# Student_Arm.net
KiCad netlist of a schematic drawn in Altium Designer
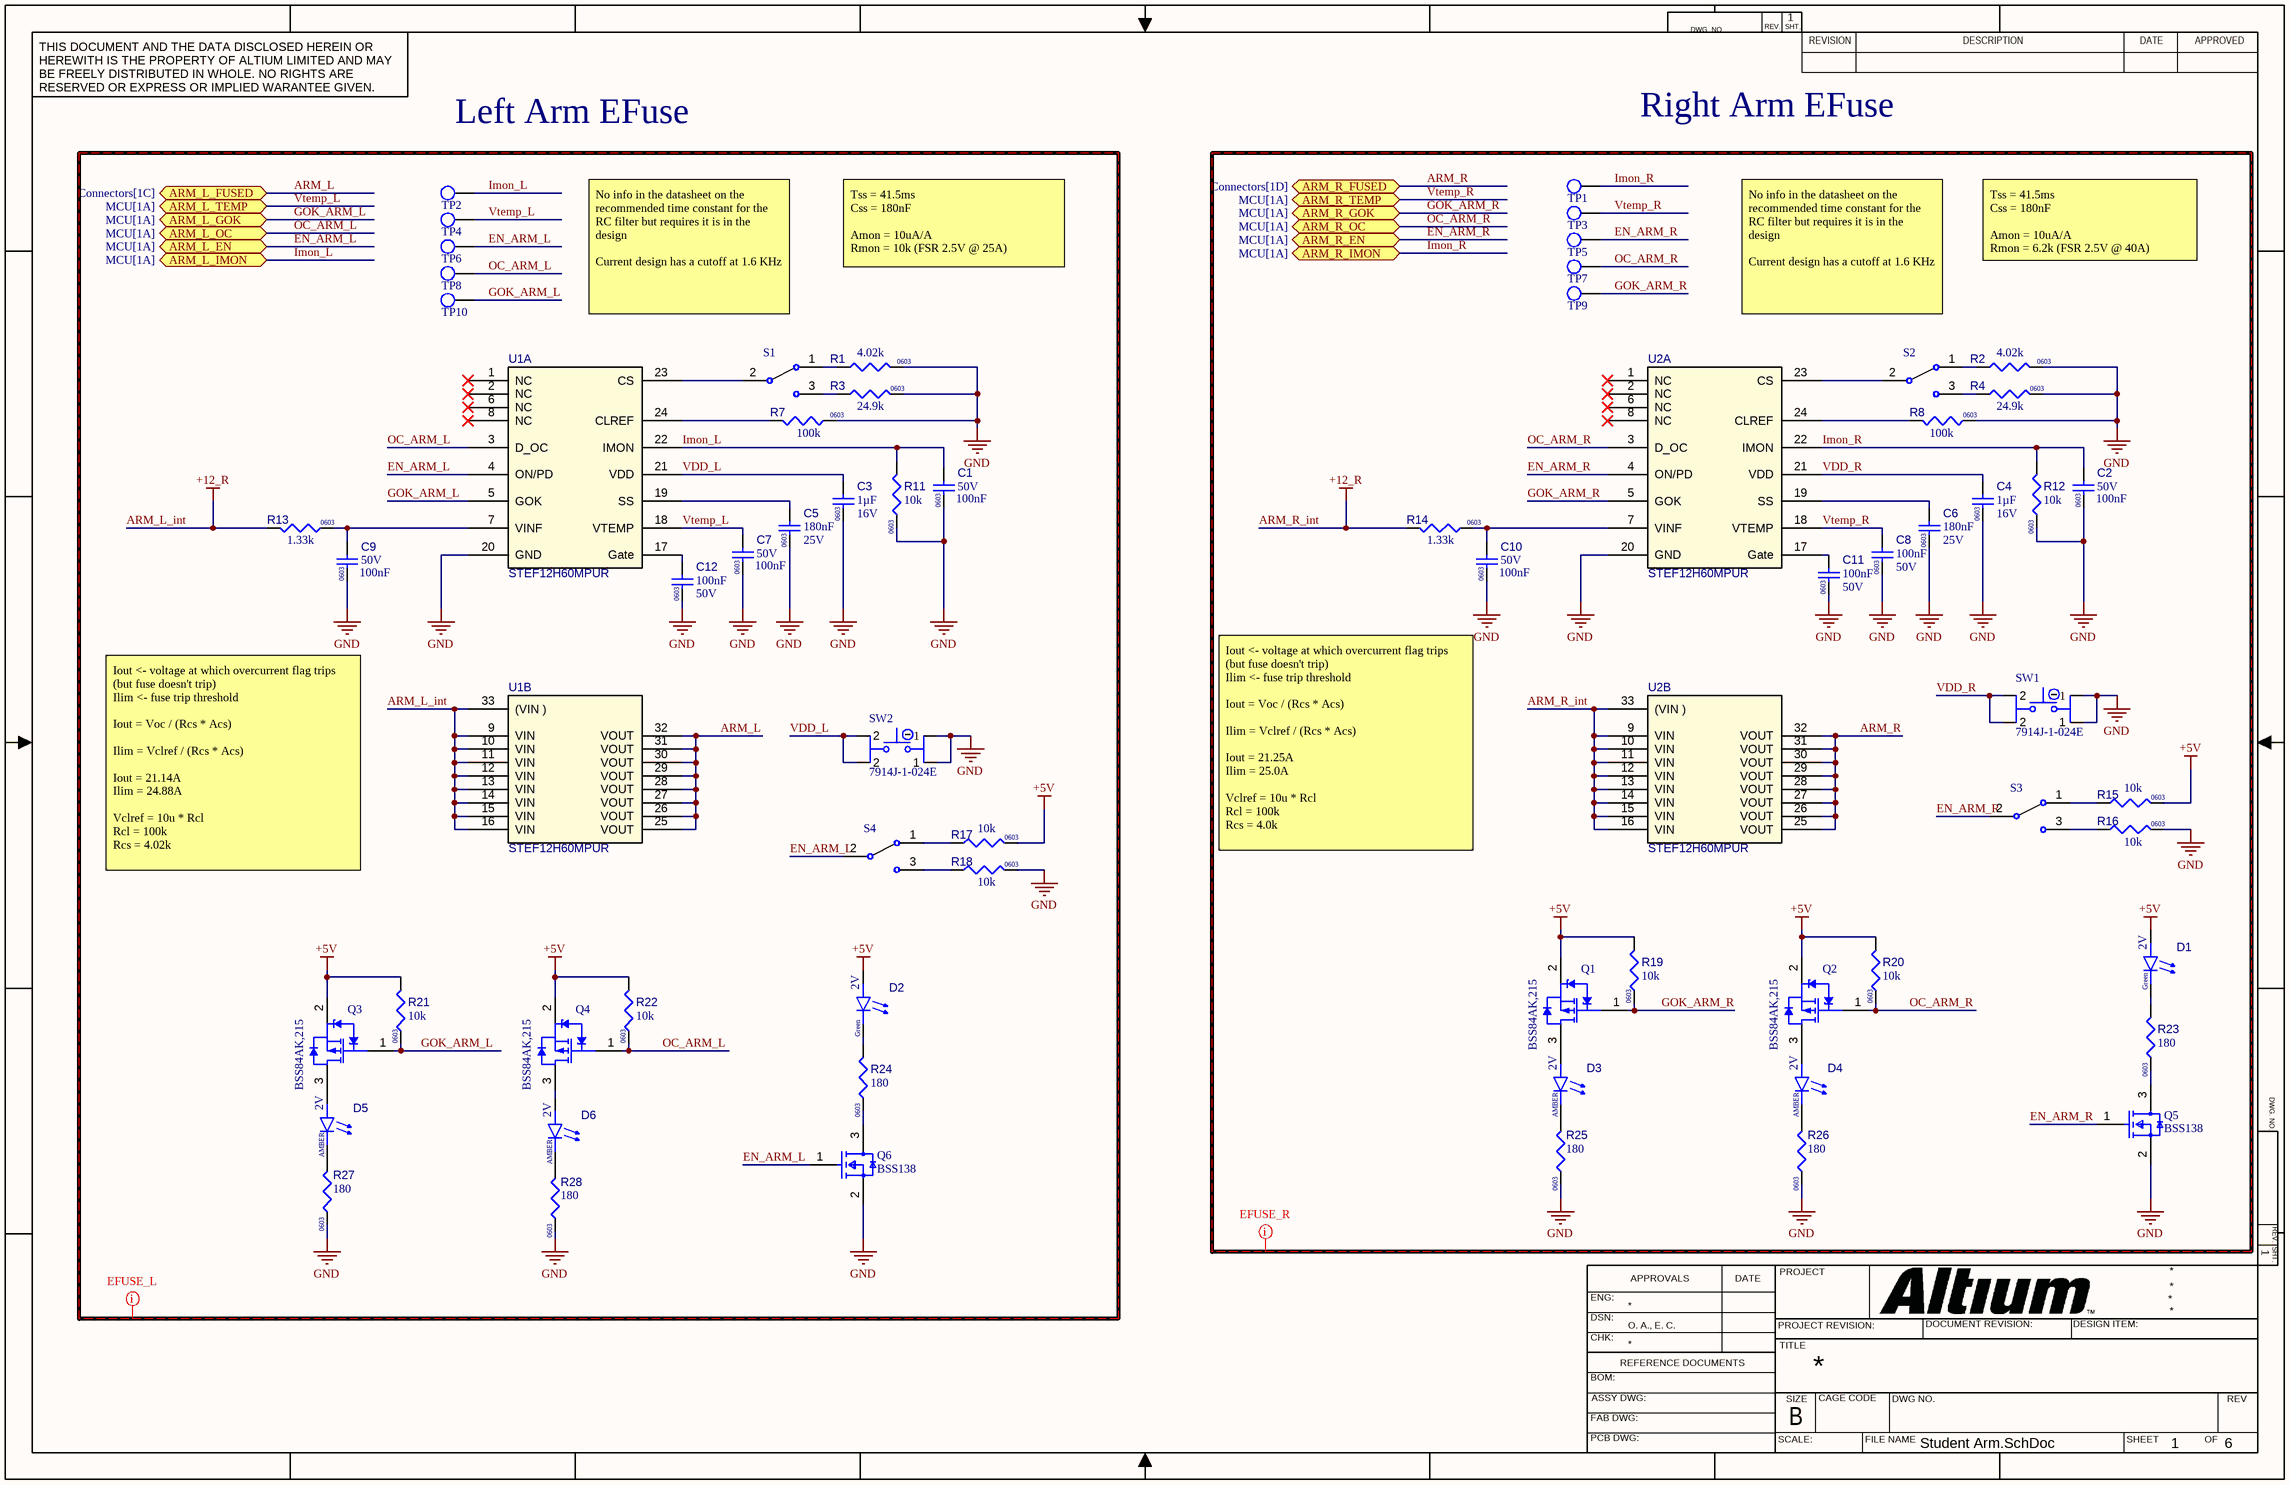
[diagram p0: Student Arm.SchDoc]

(export (version "E")
  (design (tool "Eeschema 10.0.6"))
  (components
    (comp (ref "C1")
      (value "100nF")
      (footprint "CAPC1608X90X40NL10T20")
      (description "Chip Capacitor, 100 nF, +/- 10%, 50 V, 0603 (1608 Metric)")
      (fields
        (field (name "TOLERANCE") "10%")
        (field (name "VOLTAGE RATING") "50V")
        (field (name "CASE/PACKAGE") "0603")
        (field (name "Comment") "Capacitor 100 nF +/-10% 50 V 0603")
      )
      (libsource (lib "hawaiirobotics") (part "CAP-NP-2"))
    )
    (comp (ref "C2")
      (value "100nF")
      (footprint "CAPC1608X90X40NL10T20")
      (description "Chip Capacitor, 100 nF, +/- 10%, 50 V, 0603 (1608 Metric)")
      (fields
        (field (name "TOLERANCE") "10%")
        (field (name "VOLTAGE RATING") "50V")
        (field (name "CASE/PACKAGE") "0603")
        (field (name "Comment") "Capacitor 100 nF +/-10% 50 V 0603")
      )
      (libsource (lib "hawaiirobotics") (part "CAP-NP-2"))
    )
    (comp (ref "C3")
      (value "1µF")
      (footprint "CAPC1608X90X35NL15T15")
      (description "Chip Capacitor, 1 uF, +/- 10%, 16 V, 0603 (1608 Metric)")
      (fields
        (field (name "CASE/PACKAGE") "0603")
        (field (name "TOLERANCE") "10%")
        (field (name "VOLTAGE RATING") "16V")
        (field (name "Comment") "Capacitor 1uF +/- 10% 16V 0603")
      )
      (libsource (lib "hawaiirobotics") (part "CAP-NP-2"))
    )
    (comp (ref "C4")
      (value "1µF")
      (footprint "CAPC1608X90X35NL15T15")
      (description "Chip Capacitor, 1 uF, +/- 10%, 16 V, 0603 (1608 Metric)")
      (fields
        (field (name "CASE/PACKAGE") "0603")
        (field (name "TOLERANCE") "10%")
        (field (name "VOLTAGE RATING") "16V")
        (field (name "Comment") "Capacitor 1uF +/- 10% 16V 0603")
      )
      (libsource (lib "hawaiirobotics") (part "CAP-NP-2"))
    )
    (comp (ref "C5")
      (value "180nF")
      (footprint "FP-GCM188-0_1-IPC_C")
      (fields
        (field (name "CASE/PACKAGE") "0603")
        (field (name "RATED DC VOLTAGE (URDC)") "25V")
        (field (name "Comment") "GCM188R71E184KA55D")
      )
      (libsource (lib "hawaiirobotics") (part "CAP-NP-2"))
    )
    (comp (ref "C6")
      (value "180nF")
      (footprint "FP-GCM188-0_1-IPC_C")
      (fields
        (field (name "CASE/PACKAGE") "0603")
        (field (name "RATED DC VOLTAGE (URDC)") "25V")
        (field (name "Comment") "GCM188R71E184KA55D")
      )
      (libsource (lib "hawaiirobotics") (part "CAP-NP-2"))
    )
    (comp (ref "C7")
      (value "100nF")
      (footprint "CAPC1608X90X40NL10T20")
      (description "Chip Capacitor, 100 nF, +/- 10%, 50 V, 0603 (1608 Metric)")
      (fields
        (field (name "TOLERANCE") "10%")
        (field (name "VOLTAGE RATING") "50V")
        (field (name "CASE/PACKAGE") "0603")
        (field (name "Comment") "Capacitor 100 nF +/-10% 50 V 0603")
      )
      (libsource (lib "hawaiirobotics") (part "CAP-NP-2"))
    )
    (comp (ref "C8")
      (value "100nF")
      (footprint "CAPC1608X90X40NL10T20")
      (description "Chip Capacitor, 100 nF, +/- 10%, 50 V, 0603 (1608 Metric)")
      (fields
        (field (name "TOLERANCE") "10%")
        (field (name "VOLTAGE RATING") "50V")
        (field (name "CASE/PACKAGE") "0603")
        (field (name "Comment") "Capacitor 100 nF +/-10% 50 V 0603")
      )
      (libsource (lib "hawaiirobotics") (part "CAP-NP-2"))
    )
    (comp (ref "C9")
      (value "100nF")
      (footprint "CAPC1608X90X40NL10T20")
      (description "Chip Capacitor, 100 nF, +/- 10%, 50 V, 0603 (1608 Metric)")
      (fields
        (field (name "TOLERANCE") "10%")
        (field (name "VOLTAGE RATING") "50V")
        (field (name "CASE/PACKAGE") "0603")
        (field (name "Comment") "Capacitor 100 nF +/-10% 50 V 0603")
      )
      (libsource (lib "hawaiirobotics") (part "CAP-NP-2"))
    )
    (comp (ref "C10")
      (value "100nF")
      (footprint "CAPC1608X90X40NL10T20")
      (description "Chip Capacitor, 100 nF, +/- 10%, 50 V, 0603 (1608 Metric)")
      (fields
        (field (name "TOLERANCE") "10%")
        (field (name "VOLTAGE RATING") "50V")
        (field (name "CASE/PACKAGE") "0603")
        (field (name "Comment") "Capacitor 100 nF +/-10% 50 V 0603")
      )
      (libsource (lib "hawaiirobotics") (part "CAP-NP-2"))
    )
    (comp (ref "C11")
      (value "100nF")
      (footprint "CAPC1608X90X40NL10T20")
      (description "Chip Capacitor, 100 nF, +/- 10%, 50 V, 0603 (1608 Metric)")
      (fields
        (field (name "TOLERANCE") "10%")
        (field (name "VOLTAGE RATING") "50V")
        (field (name "CASE/PACKAGE") "0603")
        (field (name "Comment") "Capacitor 100 nF +/-10% 50 V 0603")
      )
      (libsource (lib "hawaiirobotics") (part "CAP-NP-2"))
    )
    (comp (ref "C12")
      (value "100nF")
      (footprint "CAPC1608X90X40NL10T20")
      (description "Chip Capacitor, 100 nF, +/- 10%, 50 V, 0603 (1608 Metric)")
      (fields
        (field (name "TOLERANCE") "10%")
        (field (name "VOLTAGE RATING") "50V")
        (field (name "CASE/PACKAGE") "0603")
        (field (name "Comment") "Capacitor 100 nF +/-10% 50 V 0603")
      )
      (libsource (lib "hawaiirobotics") (part "CAP-NP-2"))
    )
    (comp (ref "D1")
      (value "150060VS75000")
      (footprint "WL-SMCW_0603_150060xx75000")
      (description "Single Color LED, Bright Green, Water Clear, 1.1mm")
      (fields (field (name "FORWARD VOLTAGE") "2V") (field (name "COLOR") "Green"))
      (libsource (lib "hawaiirobotics") (part "DIODE-LED-2"))
    )
    (comp (ref "D2")
      (value "150060VS75000")
      (footprint "WL-SMCW_0603_150060xx75000")
      (description "Single Color LED, Bright Green, Water Clear, 1.1mm")
      (fields (field (name "FORWARD VOLTAGE") "2V") (field (name "COLOR") "Green"))
      (libsource (lib "hawaiirobotics") (part "DIODE-LED-2"))
    )
    (comp (ref "D3")
      (value "150060AS75000")
      (footprint "WL-SMCW_0603_150060xx75000")
      (description "Single Color LED, Amber, Water Clear, 1.1mm")
      (fields (field (name "FORWARD VOLTAGE") "2V") (field (name "COLOUR") "AMBER"))
      (libsource (lib "hawaiirobotics") (part "DIODE-LED-2"))
    )
    (comp (ref "D4")
      (value "150060AS75000")
      (footprint "WL-SMCW_0603_150060xx75000")
      (description "Single Color LED, Amber, Water Clear, 1.1mm")
      (fields (field (name "FORWARD VOLTAGE") "2V") (field (name "COLOUR") "AMBER"))
      (libsource (lib "hawaiirobotics") (part "DIODE-LED-2"))
    )
    (comp (ref "D5")
      (value "150060AS75000")
      (footprint "WL-SMCW_0603_150060xx75000")
      (description "Single Color LED, Amber, Water Clear, 1.1mm")
      (fields (field (name "FORWARD VOLTAGE") "2V") (field (name "COLOUR") "AMBER"))
      (libsource (lib "hawaiirobotics") (part "DIODE-LED-2"))
    )
    (comp (ref "D6")
      (value "150060AS75000")
      (footprint "WL-SMCW_0603_150060xx75000")
      (description "Single Color LED, Amber, Water Clear, 1.1mm")
      (fields (field (name "FORWARD VOLTAGE") "2V") (field (name "COLOUR") "AMBER"))
      (libsource (lib "hawaiirobotics") (part "DIODE-LED-2"))
    )
    (comp (ref "Q1")
      (value "BSS84AK,215")
      (footprint "NXP-SOT23_N")
      (description "P-Channel Trench MOSFET, -50 V, -0.18 A, -55 to 150 degC, 3-Pin SOT23, Tape and Reel")
      (fields (field (name "MANUFACTURER") "NXP Semiconductors"))
      (libsource (lib "Altium Content Vault") (part "NXP-PMOS-GSD-3_B"))
    )
    (comp (ref "Q2")
      (value "BSS84AK,215")
      (footprint "NXP-SOT23_N")
      (description "P-Channel Trench MOSFET, -50 V, -0.18 A, -55 to 150 degC, 3-Pin SOT23, Tape and Reel")
      (fields (field (name "MANUFACTURER") "NXP Semiconductors"))
      (libsource (lib "Altium Content Vault") (part "NXP-PMOS-GSD-3_B"))
    )
    (comp (ref "Q3")
      (value "BSS84AK,215")
      (footprint "NXP-SOT23_N")
      (description "P-Channel Trench MOSFET, -50 V, -0.18 A, -55 to 150 degC, 3-Pin SOT23, Tape and Reel")
      (fields (field (name "MANUFACTURER") "NXP Semiconductors"))
      (libsource (lib "Altium Content Vault") (part "NXP-PMOS-GSD-3_B"))
    )
    (comp (ref "Q4")
      (value "BSS84AK,215")
      (footprint "NXP-SOT23_N")
      (description "P-Channel Trench MOSFET, -50 V, -0.18 A, -55 to 150 degC, 3-Pin SOT23, Tape and Reel")
      (fields (field (name "MANUFACTURER") "NXP Semiconductors"))
      (libsource (lib "Altium Content Vault") (part "NXP-PMOS-GSD-3_B"))
    )
    (comp (ref "Q5")
      (value "BSS138")
      (footprint "FP-318-08-IPC_B")
      (description "MOSFET N-CH 50V 220MA SOT-23")
      (libsource (lib "Altium Content Vault") (part "3b9c635fedb024a5347a57b145af9cc"))
    )
    (comp (ref "Q6")
      (value "BSS138")
      (footprint "FP-318-08-IPC_B")
      (description "MOSFET N-CH 50V 220MA SOT-23")
      (libsource (lib "Altium Content Vault") (part "3b9c635fedb024a5347a57b145af9cc"))
    )
    (comp (ref "R1")
      (value "4.02k")
      (footprint "RESC1608X55X25NL10T15")
      (fields
        (field (name "TOLERANCE") "1%")
        (field (name "POWER") "100mW")
        (field (name "CASE/PACKAGE") "0603")
        (field (name "Comment") "RC0603FR-074K02L")
      )
      (libsource (lib "hawaiirobotics") (part "RES-2"))
    )
    (comp (ref "R2")
      (value "4.02k")
      (footprint "RESC1608X55X25NL10T15")
      (fields
        (field (name "TOLERANCE") "1%")
        (field (name "POWER") "100mW")
        (field (name "CASE/PACKAGE") "0603")
        (field (name "Comment") "RC0603FR-074K02L")
      )
      (libsource (lib "hawaiirobotics") (part "RES-2"))
    )
    (comp (ref "R3")
      (value "24.9k")
      (footprint "RESC1608X55X25NL10T15")
      (fields
        (field (name "POWER") "100mW")
        (field (name "TOLERANCE") "1%")
        (field (name "CASE/PACKAGE") "0603")
        (field (name "Comment") "RC0603FR-1024K9L")
      )
      (libsource (lib "hawaiirobotics") (part "RES-2"))
    )
    (comp (ref "R4")
      (value "24.9k")
      (footprint "RESC1608X55X25NL10T15")
      (fields
        (field (name "POWER") "100mW")
        (field (name "TOLERANCE") "1%")
        (field (name "CASE/PACKAGE") "0603")
        (field (name "Comment") "RC0603FR-1024K9L")
      )
      (libsource (lib "hawaiirobotics") (part "RES-2"))
    )
    (comp (ref "R7")
      (value "100k")
      (footprint "RESC1608X55X25NL10T15")
      (fields
        (field (name "POWER") "100mW")
        (field (name "TOLERANCE") "1%")
        (field (name "CASE/PACKAGE") "0603")
        (field (name "Comment") "RC0603FR-07100KL")
      )
      (libsource (lib "hawaiirobotics") (part "RES-2"))
    )
    (comp (ref "R8")
      (value "100k")
      (footprint "RESC1608X55X25NL10T15")
      (fields
        (field (name "POWER") "100mW")
        (field (name "TOLERANCE") "1%")
        (field (name "CASE/PACKAGE") "0603")
        (field (name "Comment") "RC0603FR-07100KL")
      )
      (libsource (lib "hawaiirobotics") (part "RES-2"))
    )
    (comp (ref "R11")
      (value "10k")
      (footprint "RESC1608X55X25NL10T15")
      (description "Chip Resistor, 10 KOhm, +/- 1%, 01 W, -55 to 155 degC, 0603 (1608 Metric)")
      (fields
        (field (name "CASE/PACKAGE") "0603")
        (field (name "POWER") "100mW")
        (field (name "TOLERANCE") "1%")
      )
      (libsource (lib "hawaiirobotics") (part "RES-2"))
    )
    (comp (ref "R12")
      (value "10k")
      (footprint "RESC1608X55X25NL10T15")
      (description "Chip Resistor, 10 KOhm, +/- 1%, 01 W, -55 to 155 degC, 0603 (1608 Metric)")
      (fields
        (field (name "CASE/PACKAGE") "0603")
        (field (name "POWER") "100mW")
        (field (name "TOLERANCE") "1%")
      )
      (libsource (lib "hawaiirobotics") (part "RES-2"))
    )
    (comp (ref "R13")
      (value "1.33k")
      (footprint "RESC1608X55X25NL10T15")
      (fields
        (field (name "TOLERANCE") "1%")
        (field (name "CASE/PACKAGE") "0603")
        (field (name "POWER") "100mW")
        (field (name "Comment") "RC0603FR-071K33L")
      )
      (libsource (lib "hawaiirobotics") (part "RES-2"))
    )
    (comp (ref "R14")
      (value "1.33k")
      (footprint "RESC1608X55X25NL10T15")
      (fields
        (field (name "TOLERANCE") "1%")
        (field (name "CASE/PACKAGE") "0603")
        (field (name "POWER") "100mW")
        (field (name "Comment") "RC0603FR-071K33L")
      )
      (libsource (lib "hawaiirobotics") (part "RES-2"))
    )
    (comp (ref "R15")
      (value "10k")
      (footprint "RESC1608X55X25NL10T15")
      (description "Chip Resistor, 10 KOhm, +/- 1%, 01 W, -55 to 155 degC, 0603 (1608 Metric)")
      (fields
        (field (name "CASE/PACKAGE") "0603")
        (field (name "POWER") "100mW")
        (field (name "TOLERANCE") "1%")
      )
      (libsource (lib "hawaiirobotics") (part "RES-2"))
    )
    (comp (ref "R16")
      (value "10k")
      (footprint "RESC1608X55X25NL10T15")
      (description "Chip Resistor, 10 KOhm, +/- 1%, 01 W, -55 to 155 degC, 0603 (1608 Metric)")
      (fields
        (field (name "CASE/PACKAGE") "0603")
        (field (name "POWER") "100mW")
        (field (name "TOLERANCE") "1%")
      )
      (libsource (lib "hawaiirobotics") (part "RES-2"))
    )
    (comp (ref "R17")
      (value "10k")
      (footprint "RESC1608X55X25NL10T15")
      (description "Chip Resistor, 10 KOhm, +/- 1%, 01 W, -55 to 155 degC, 0603 (1608 Metric)")
      (fields
        (field (name "CASE/PACKAGE") "0603")
        (field (name "POWER") "100mW")
        (field (name "TOLERANCE") "1%")
      )
      (libsource (lib "hawaiirobotics") (part "RES-2"))
    )
    (comp (ref "R18")
      (value "10k")
      (footprint "RESC1608X55X25NL10T15")
      (description "Chip Resistor, 10 KOhm, +/- 1%, 01 W, -55 to 155 degC, 0603 (1608 Metric)")
      (fields
        (field (name "CASE/PACKAGE") "0603")
        (field (name "POWER") "100mW")
        (field (name "TOLERANCE") "1%")
      )
      (libsource (lib "hawaiirobotics") (part "RES-2"))
    )
    (comp (ref "R19")
      (value "10k")
      (footprint "RESC1608X55X25NL10T15")
      (description "Chip Resistor, 10 KOhm, +/- 1%, 01 W, -55 to 155 degC, 0603 (1608 Metric)")
      (fields
        (field (name "CASE/PACKAGE") "0603")
        (field (name "POWER") "100mW")
        (field (name "TOLERANCE") "1%")
      )
      (libsource (lib "hawaiirobotics") (part "RES-2"))
    )
    (comp (ref "R20")
      (value "10k")
      (footprint "RESC1608X55X25NL10T15")
      (description "Chip Resistor, 10 KOhm, +/- 1%, 01 W, -55 to 155 degC, 0603 (1608 Metric)")
      (fields
        (field (name "CASE/PACKAGE") "0603")
        (field (name "POWER") "100mW")
        (field (name "TOLERANCE") "1%")
      )
      (libsource (lib "hawaiirobotics") (part "RES-2"))
    )
    (comp (ref "R21")
      (value "10k")
      (footprint "RESC1608X55X25NL10T15")
      (description "Chip Resistor, 10 KOhm, +/- 1%, 01 W, -55 to 155 degC, 0603 (1608 Metric)")
      (fields
        (field (name "CASE/PACKAGE") "0603")
        (field (name "POWER") "100mW")
        (field (name "TOLERANCE") "1%")
      )
      (libsource (lib "hawaiirobotics") (part "RES-2"))
    )
    (comp (ref "R22")
      (value "10k")
      (footprint "RESC1608X55X25NL10T15")
      (description "Chip Resistor, 10 KOhm, +/- 1%, 01 W, -55 to 155 degC, 0603 (1608 Metric)")
      (fields
        (field (name "CASE/PACKAGE") "0603")
        (field (name "POWER") "100mW")
        (field (name "TOLERANCE") "1%")
      )
      (libsource (lib "hawaiirobotics") (part "RES-2"))
    )
    (comp (ref "R23")
      (value "180")
      (footprint "RESC0603(1608)_N")
      (fields
        (field (name "TOLERANCE") "5%")
        (field (name "CASE/PACKAGE") "0603")
        (field (name "POWER") "100mW")
        (field (name "Comment") "RC0603JR-07180RL")
      )
      (libsource (lib "hawaiirobotics") (part "RES-2"))
    )
    (comp (ref "R24")
      (value "180")
      (footprint "RESC0603(1608)_N")
      (fields
        (field (name "TOLERANCE") "5%")
        (field (name "CASE/PACKAGE") "0603")
        (field (name "POWER") "100mW")
        (field (name "Comment") "RC0603JR-07180RL")
      )
      (libsource (lib "hawaiirobotics") (part "RES-2"))
    )
    (comp (ref "R25")
      (value "180")
      (footprint "RESC0603(1608)_N")
      (fields
        (field (name "TOLERANCE") "5%")
        (field (name "CASE/PACKAGE") "0603")
        (field (name "POWER") "100mW")
        (field (name "Comment") "RC0603JR-07180RL")
      )
      (libsource (lib "hawaiirobotics") (part "RES-2"))
    )
    (comp (ref "R26")
      (value "180")
      (footprint "RESC0603(1608)_N")
      (fields
        (field (name "TOLERANCE") "5%")
        (field (name "CASE/PACKAGE") "0603")
        (field (name "POWER") "100mW")
        (field (name "Comment") "RC0603JR-07180RL")
      )
      (libsource (lib "hawaiirobotics") (part "RES-2"))
    )
    (comp (ref "R27")
      (value "180")
      (footprint "RESC0603(1608)_N")
      (fields
        (field (name "TOLERANCE") "5%")
        (field (name "CASE/PACKAGE") "0603")
        (field (name "POWER") "100mW")
        (field (name "Comment") "RC0603JR-07180RL")
      )
      (libsource (lib "hawaiirobotics") (part "RES-2"))
    )
    (comp (ref "R28")
      (value "180")
      (footprint "RESC0603(1608)_N")
      (fields
        (field (name "TOLERANCE") "5%")
        (field (name "CASE/PACKAGE") "0603")
        (field (name "POWER") "100mW")
        (field (name "Comment") "RC0603JR-07180RL")
      )
      (libsource (lib "hawaiirobotics") (part "RES-2"))
    )
    (comp (ref "S1")
      (value "SLW-883935-2A-D")
      (footprint "SLW-883935-2A-D-Footprint-1")
      (description "8.8 X 3.9 X 3.5 Mm, 2 Mm Raised")
      (libsource (lib "hawaiirobotics") (part "SLW-883935-2A-D-Symbol-1"))
    )
    (comp (ref "S2")
      (value "SLW-883935-2A-D")
      (footprint "SLW-883935-2A-D-Footprint-1")
      (description "8.8 X 3.9 X 3.5 Mm, 2 Mm Raised")
      (libsource (lib "hawaiirobotics") (part "SLW-883935-2A-D-Symbol-1"))
    )
    (comp (ref "S3")
      (value "SLW-883935-2A-D")
      (footprint "SLW-883935-2A-D-Footprint-1")
      (description "8.8 X 3.9 X 3.5 Mm, 2 Mm Raised")
      (libsource (lib "hawaiirobotics") (part "SLW-883935-2A-D-Symbol-1"))
    )
    (comp (ref "S4")
      (value "SLW-883935-2A-D")
      (footprint "SLW-883935-2A-D-Footprint-1")
      (description "8.8 X 3.9 X 3.5 Mm, 2 Mm Raised")
      (libsource (lib "hawaiirobotics") (part "SLW-883935-2A-D-Symbol-1"))
    )
    (comp (ref "SW1")
      (value "7914J-1-024E")
      (footprint "FP-7914J-1-024E-MFG")
      (libsource (lib "hawaiirobotics") (part "4aa6f850d040344456d32f8cc0a5a85"))
    )
    (comp (ref "SW2")
      (value "7914J-1-024E")
      (footprint "FP-7914J-1-024E-MFG")
      (libsource (lib "hawaiirobotics") (part "4aa6f850d040344456d32f8cc0a5a85"))
    )
    (comp (ref "TP1")
      (value "RCUCTE")
      (footprint "FP-S2761-46R-MFG")
      (description "Test point")
      (libsource (lib "hawaiirobotics") (part "RCUCTE-Symbol-1"))
    )
    (comp (ref "TP2")
      (value "RCUCTE")
      (footprint "FP-S2761-46R-MFG")
      (description "Test point")
      (libsource (lib "hawaiirobotics") (part "RCUCTE-Symbol-1"))
    )
    (comp (ref "TP3")
      (value "RCUCTE")
      (footprint "FP-S2761-46R-MFG")
      (description "Test point")
      (libsource (lib "hawaiirobotics") (part "RCUCTE-Symbol-1"))
    )
    (comp (ref "TP4")
      (value "RCUCTE")
      (footprint "FP-S2761-46R-MFG")
      (description "Test point")
      (libsource (lib "hawaiirobotics") (part "RCUCTE-Symbol-1"))
    )
    (comp (ref "TP5")
      (value "RCUCTE")
      (footprint "FP-S2761-46R-MFG")
      (description "Test point")
      (libsource (lib "hawaiirobotics") (part "RCUCTE-Symbol-1"))
    )
    (comp (ref "TP6")
      (value "RCUCTE")
      (footprint "FP-S2761-46R-MFG")
      (description "Test point")
      (libsource (lib "hawaiirobotics") (part "RCUCTE-Symbol-1"))
    )
    (comp (ref "TP7")
      (value "RCUCTE")
      (footprint "FP-S2761-46R-MFG")
      (description "Test point")
      (libsource (lib "hawaiirobotics") (part "RCUCTE-Symbol-1"))
    )
    (comp (ref "TP8")
      (value "RCUCTE")
      (footprint "FP-S2761-46R-MFG")
      (description "Test point")
      (libsource (lib "hawaiirobotics") (part "RCUCTE-Symbol-1"))
    )
    (comp (ref "TP9")
      (value "RCUCTE")
      (footprint "FP-S2761-46R-MFG")
      (description "Test point")
      (libsource (lib "hawaiirobotics") (part "RCUCTE-Symbol-1"))
    )
    (comp (ref "TP10")
      (value "RCUCTE")
      (footprint "FP-S2761-46R-MFG")
      (description "Test point")
      (libsource (lib "hawaiirobotics") (part "RCUCTE-Symbol-1"))
    )
    (comp (ref "U1")
      (value "STEF12H60MPUR")
      (footprint "STEF12H60MPUR-Footprint-1")
      (description "IC ELECTRONIC FUSE 32QFN")
      (libsource (lib "hawaiirobotics") (part "STEF12H60MPUR"))
    )
    (comp (ref "U2")
      (value "STEF12H60MPUR")
      (footprint "STEF12H60MPUR-Footprint-1")
      (description "IC ELECTRONIC FUSE 32QFN")
      (libsource (lib "hawaiirobotics") (part "STEF12H60MPUR"))
    )
  )
  (nets
    (net (code "1") (name "+5V") (class "Default")
      (node (ref "D1") (pin "2") (pinfunction "A_2") (pintype "passive"))
      (node (ref "D2") (pin "2") (pinfunction "A_2") (pintype "passive"))
      (node (ref "Q1") (pin "2") (pinfunction "S_2") (pintype "passive"))
      (node (ref "Q2") (pin "2") (pinfunction "S_2") (pintype "passive"))
      (node (ref "Q3") (pin "2") (pinfunction "S_2") (pintype "passive"))
      (node (ref "Q4") (pin "2") (pinfunction "S_2") (pintype "passive"))
      (node (ref "R15") (pin "2") (pinfunction "2_2") (pintype "passive"))
      (node (ref "R17") (pin "2") (pinfunction "2_2") (pintype "passive"))
      (node (ref "R19") (pin "2") (pinfunction "2_2") (pintype "passive"))
      (node (ref "R20") (pin "2") (pinfunction "2_2") (pintype "passive"))
      (node (ref "R21") (pin "2") (pinfunction "2_2") (pintype "passive"))
      (node (ref "R22") (pin "2") (pinfunction "2_2") (pintype "passive"))
    )
    (net (code "2") (name "+12_R") (class "Default")
      (node (ref "R13") (pin "2") (pinfunction "2_2") (pintype "passive"))
      (node (ref "R14") (pin "2") (pinfunction "2_2") (pintype "passive"))
      (node (ref "U1") (pin "10") (pinfunction "VIN_10") (pintype "power_in"))
      (node (ref "U1") (pin "11") (pinfunction "VIN_11") (pintype "power_in"))
      (node (ref "U1") (pin "12") (pinfunction "VIN_12") (pintype "power_in"))
      (node (ref "U1") (pin "13") (pinfunction "VIN_13") (pintype "power_in"))
      (node (ref "U1") (pin "14") (pinfunction "VIN_14") (pintype "power_in"))
      (node (ref "U1") (pin "15") (pinfunction "VIN_15") (pintype "power_in"))
      (node (ref "U1") (pin "16") (pinfunction "VIN_16") (pintype "power_in"))
      (node (ref "U1") (pin "33") (pinfunction "(VIN_)_33") (pintype "power_in"))
      (node (ref "U1") (pin "9") (pinfunction "VIN_9") (pintype "power_in"))
      (node (ref "U2") (pin "10") (pinfunction "VIN_10") (pintype "power_in"))
      (node (ref "U2") (pin "11") (pinfunction "VIN_11") (pintype "power_in"))
      (node (ref "U2") (pin "12") (pinfunction "VIN_12") (pintype "power_in"))
      (node (ref "U2") (pin "13") (pinfunction "VIN_13") (pintype "power_in"))
      (node (ref "U2") (pin "14") (pinfunction "VIN_14") (pintype "power_in"))
      (node (ref "U2") (pin "15") (pinfunction "VIN_15") (pintype "power_in"))
      (node (ref "U2") (pin "16") (pinfunction "VIN_16") (pintype "power_in"))
      (node (ref "U2") (pin "33") (pinfunction "(VIN_)_33") (pintype "power_in"))
      (node (ref "U2") (pin "9") (pinfunction "VIN_9") (pintype "power_in"))
    )
    (net (code "3") (name "/ARM_L") (class "Default")
      (node (ref "U1") (pin "25") (pinfunction "VOUT_25") (pintype "power_in"))
      (node (ref "U1") (pin "26") (pinfunction "VOUT_26") (pintype "power_in"))
      (node (ref "U1") (pin "27") (pinfunction "VOUT_27") (pintype "power_in"))
      (node (ref "U1") (pin "28") (pinfunction "VOUT_28") (pintype "power_in"))
      (node (ref "U1") (pin "29") (pinfunction "VOUT_29") (pintype "power_in"))
      (node (ref "U1") (pin "30") (pinfunction "VOUT_30") (pintype "power_in"))
      (node (ref "U1") (pin "31") (pinfunction "VOUT_31") (pintype "power_in"))
      (node (ref "U1") (pin "32") (pinfunction "VOUT_32") (pintype "power_in"))
    )
    (net (code "4") (name "/ARM_R") (class "Default")
      (node (ref "U2") (pin "25") (pinfunction "VOUT_25") (pintype "power_in"))
      (node (ref "U2") (pin "26") (pinfunction "VOUT_26") (pintype "power_in"))
      (node (ref "U2") (pin "27") (pinfunction "VOUT_27") (pintype "power_in"))
      (node (ref "U2") (pin "28") (pinfunction "VOUT_28") (pintype "power_in"))
      (node (ref "U2") (pin "29") (pinfunction "VOUT_29") (pintype "power_in"))
      (node (ref "U2") (pin "30") (pinfunction "VOUT_30") (pintype "power_in"))
      (node (ref "U2") (pin "31") (pinfunction "VOUT_31") (pintype "power_in"))
      (node (ref "U2") (pin "32") (pinfunction "VOUT_32") (pintype "power_in"))
    )
    (net (code "5") (name "/EN_ARM_L") (class "Default")
      (node (ref "Q6") (pin "1") (pinfunction "G_1") (pintype "passive"))
      (node (ref "S4") (pin "2") (pinfunction "COM_2") (pintype "passive"))
      (node (ref "TP6") (pin "1") (pinfunction "1_1") (pintype "passive"))
      (node (ref "U1") (pin "4") (pinfunction "ON/PD_4") (pintype "passive"))
    )
    (net (code "6") (name "/EN_ARM_R") (class "Default")
      (node (ref "Q5") (pin "1") (pinfunction "G_1") (pintype "passive"))
      (node (ref "S3") (pin "2") (pinfunction "COM_2") (pintype "passive"))
      (node (ref "TP5") (pin "1") (pinfunction "1_1") (pintype "passive"))
      (node (ref "U2") (pin "4") (pinfunction "ON/PD_4") (pintype "passive"))
    )
    (net (code "7") (name "/GOK_ARM_L") (class "Default")
      (node (ref "Q3") (pin "1") (pinfunction "G_1") (pintype "passive"))
      (node (ref "R21") (pin "1") (pinfunction "1_1") (pintype "passive"))
      (node (ref "TP10") (pin "1") (pinfunction "1_1") (pintype "passive"))
      (node (ref "U1") (pin "5") (pinfunction "GOK_5") (pintype "passive"))
    )
    (net (code "8") (name "/GOK_ARM_R") (class "Default")
      (node (ref "Q1") (pin "1") (pinfunction "G_1") (pintype "passive"))
      (node (ref "R19") (pin "1") (pinfunction "1_1") (pintype "passive"))
      (node (ref "TP9") (pin "1") (pinfunction "1_1") (pintype "passive"))
      (node (ref "U2") (pin "5") (pinfunction "GOK_5") (pintype "passive"))
    )
    (net (code "9") (name "/Imon_L") (class "Default")
      (node (ref "C1") (pin "2") (pinfunction "2_2") (pintype "passive"))
      (node (ref "R11") (pin "2") (pinfunction "2_2") (pintype "passive"))
      (node (ref "TP2") (pin "1") (pinfunction "1_1") (pintype "passive"))
      (node (ref "U1") (pin "22") (pinfunction "IMON_22") (pintype "passive"))
    )
    (net (code "10") (name "/Imon_R") (class "Default")
      (node (ref "C2") (pin "2") (pinfunction "2_2") (pintype "passive"))
      (node (ref "R12") (pin "2") (pinfunction "2_2") (pintype "passive"))
      (node (ref "TP1") (pin "1") (pinfunction "1_1") (pintype "passive"))
      (node (ref "U2") (pin "22") (pinfunction "IMON_22") (pintype "passive"))
    )
    (net (code "11") (name "/OC_ARM_L") (class "Default")
      (node (ref "Q4") (pin "1") (pinfunction "G_1") (pintype "passive"))
      (node (ref "R22") (pin "1") (pinfunction "1_1") (pintype "passive"))
      (node (ref "TP8") (pin "1") (pinfunction "1_1") (pintype "passive"))
      (node (ref "U1") (pin "3") (pinfunction "D_OC_3") (pintype "passive"))
    )
    (net (code "12") (name "/OC_ARM_R") (class "Default")
      (node (ref "Q2") (pin "1") (pinfunction "G_1") (pintype "passive"))
      (node (ref "R20") (pin "1") (pinfunction "1_1") (pintype "passive"))
      (node (ref "TP7") (pin "1") (pinfunction "1_1") (pintype "passive"))
      (node (ref "U2") (pin "3") (pinfunction "D_OC_3") (pintype "passive"))
    )
    (net (code "13") (name "/VDD_L") (class "Default")
      (node (ref "C3") (pin "2") (pinfunction "2_2") (pintype "passive"))
      (node (ref "SW2") (pin "2") (pinfunction "2_2") (pintype "passive"))
      (node (ref "SW2") (pin "3") (pinfunction "2_3") (pintype "passive"))
      (node (ref "U1") (pin "21") (pinfunction "VDD_21") (pintype "power_in"))
    )
    (net (code "14") (name "/VDD_R") (class "Default")
      (node (ref "C4") (pin "2") (pinfunction "2_2") (pintype "passive"))
      (node (ref "SW1") (pin "2") (pinfunction "2_2") (pintype "passive"))
      (node (ref "SW1") (pin "3") (pinfunction "2_3") (pintype "passive"))
      (node (ref "U2") (pin "21") (pinfunction "VDD_21") (pintype "power_in"))
    )
    (net (code "15") (name "/Vtemp_L") (class "Default")
      (node (ref "C7") (pin "2") (pinfunction "2_2") (pintype "passive"))
      (node (ref "TP4") (pin "1") (pinfunction "1_1") (pintype "passive"))
      (node (ref "U1") (pin "18") (pinfunction "VTEMP_18") (pintype "passive"))
    )
    (net (code "16") (name "/Vtemp_R") (class "Default")
      (node (ref "C8") (pin "2") (pinfunction "2_2") (pintype "passive"))
      (node (ref "TP3") (pin "1") (pinfunction "1_1") (pintype "passive"))
      (node (ref "U2") (pin "18") (pinfunction "VTEMP_18") (pintype "passive"))
    )
    (net (code "17") (name "GND") (class "Default")
      (node (ref "C1") (pin "1") (pinfunction "1_1") (pintype "passive"))
      (node (ref "C10") (pin "1") (pinfunction "1_1") (pintype "passive"))
      (node (ref "C11") (pin "1") (pinfunction "1_1") (pintype "passive"))
      (node (ref "C12") (pin "1") (pinfunction "1_1") (pintype "passive"))
      (node (ref "C2") (pin "1") (pinfunction "1_1") (pintype "passive"))
      (node (ref "C3") (pin "1") (pinfunction "1_1") (pintype "passive"))
      (node (ref "C4") (pin "1") (pinfunction "1_1") (pintype "passive"))
      (node (ref "C5") (pin "1") (pinfunction "1_1") (pintype "passive"))
      (node (ref "C6") (pin "1") (pinfunction "1_1") (pintype "passive"))
      (node (ref "C7") (pin "1") (pinfunction "1_1") (pintype "passive"))
      (node (ref "C8") (pin "1") (pinfunction "1_1") (pintype "passive"))
      (node (ref "C9") (pin "1") (pinfunction "1_1") (pintype "passive"))
      (node (ref "Q5") (pin "2") (pinfunction "S_2") (pintype "passive"))
      (node (ref "Q6") (pin "2") (pinfunction "S_2") (pintype "passive"))
      (node (ref "R1") (pin "2") (pinfunction "2_2") (pintype "passive"))
      (node (ref "R11") (pin "1") (pinfunction "1_1") (pintype "passive"))
      (node (ref "R12") (pin "1") (pinfunction "1_1") (pintype "passive"))
      (node (ref "R16") (pin "2") (pinfunction "2_2") (pintype "passive"))
      (node (ref "R18") (pin "2") (pinfunction "2_2") (pintype "passive"))
      (node (ref "R2") (pin "2") (pinfunction "2_2") (pintype "passive"))
      (node (ref "R25") (pin "1") (pinfunction "1_1") (pintype "passive"))
      (node (ref "R26") (pin "1") (pinfunction "1_1") (pintype "passive"))
      (node (ref "R27") (pin "1") (pinfunction "1_1") (pintype "passive"))
      (node (ref "R28") (pin "1") (pinfunction "1_1") (pintype "passive"))
      (node (ref "R3") (pin "2") (pinfunction "2_2") (pintype "passive"))
      (node (ref "R4") (pin "2") (pinfunction "2_2") (pintype "passive"))
      (node (ref "R7") (pin "1") (pinfunction "1_1") (pintype "passive"))
      (node (ref "R8") (pin "1") (pinfunction "1_1") (pintype "passive"))
      (node (ref "SW1") (pin "1") (pinfunction "1_1") (pintype "passive"))
      (node (ref "SW1") (pin "4") (pinfunction "1_4") (pintype "passive"))
      (node (ref "SW2") (pin "1") (pinfunction "1_1") (pintype "passive"))
      (node (ref "SW2") (pin "4") (pinfunction "1_4") (pintype "passive"))
      (node (ref "U1") (pin "20") (pinfunction "GND_20") (pintype "power_in"))
      (node (ref "U2") (pin "20") (pinfunction "GND_20") (pintype "power_in"))
    )
    (net (code "18") (name "Net-(D1-K)") (class "Default")
      (node (ref "D1") (pin "1") (pinfunction "K_1") (pintype "passive"))
      (node (ref "R23") (pin "2") (pinfunction "2_2") (pintype "passive"))
    )
    (net (code "19") (name "Net-(D2-K)") (class "Default")
      (node (ref "D2") (pin "1") (pinfunction "K_1") (pintype "passive"))
      (node (ref "R24") (pin "2") (pinfunction "2_2") (pintype "passive"))
    )
    (net (code "20") (name "Net-(D3-A)") (class "Default")
      (node (ref "D3") (pin "2") (pinfunction "A_2") (pintype "passive"))
      (node (ref "Q1") (pin "3") (pinfunction "D_3") (pintype "passive"))
    )
    (net (code "21") (name "Net-(D3-K)") (class "Default")
      (node (ref "D3") (pin "1") (pinfunction "K_1") (pintype "passive"))
      (node (ref "R25") (pin "2") (pinfunction "2_2") (pintype "passive"))
    )
    (net (code "22") (name "Net-(D4-A)") (class "Default")
      (node (ref "D4") (pin "2") (pinfunction "A_2") (pintype "passive"))
      (node (ref "Q2") (pin "3") (pinfunction "D_3") (pintype "passive"))
    )
    (net (code "23") (name "Net-(D4-K)") (class "Default")
      (node (ref "D4") (pin "1") (pinfunction "K_1") (pintype "passive"))
      (node (ref "R26") (pin "2") (pinfunction "2_2") (pintype "passive"))
    )
    (net (code "24") (name "Net-(D5-A)") (class "Default")
      (node (ref "D5") (pin "2") (pinfunction "A_2") (pintype "passive"))
      (node (ref "Q3") (pin "3") (pinfunction "D_3") (pintype "passive"))
    )
    (net (code "25") (name "Net-(D5-K)") (class "Default")
      (node (ref "D5") (pin "1") (pinfunction "K_1") (pintype "passive"))
      (node (ref "R27") (pin "2") (pinfunction "2_2") (pintype "passive"))
    )
    (net (code "26") (name "Net-(D6-A)") (class "Default")
      (node (ref "D6") (pin "2") (pinfunction "A_2") (pintype "passive"))
      (node (ref "Q4") (pin "3") (pinfunction "D_3") (pintype "passive"))
    )
    (net (code "27") (name "Net-(D6-K)") (class "Default")
      (node (ref "D6") (pin "1") (pinfunction "K_1") (pintype "passive"))
      (node (ref "R28") (pin "2") (pinfunction "2_2") (pintype "passive"))
    )
    (net (code "28") (name "Net-(Q5-D)") (class "Default")
      (node (ref "Q5") (pin "3") (pinfunction "D_3") (pintype "passive"))
      (node (ref "R23") (pin "1") (pinfunction "1_1") (pintype "passive"))
    )
    (net (code "29") (name "Net-(Q6-D)") (class "Default")
      (node (ref "Q6") (pin "3") (pinfunction "D_3") (pintype "passive"))
      (node (ref "R24") (pin "1") (pinfunction "1_1") (pintype "passive"))
    )
    (net (code "30") (name "Net-(S1-COM)") (class "Default")
      (node (ref "S1") (pin "2") (pinfunction "COM_2") (pintype "passive"))
      (node (ref "U1") (pin "23") (pinfunction "CS_23") (pintype "passive"))
    )
    (net (code "31") (name "Net-(S1-NC)") (class "Default")
      (node (ref "R1") (pin "1") (pinfunction "1_1") (pintype "passive"))
      (node (ref "S1") (pin "1") (pinfunction "NC_1") (pintype "passive"))
    )
    (net (code "32") (name "Net-(S1-NO)") (class "Default")
      (node (ref "R3") (pin "1") (pinfunction "1_1") (pintype "passive"))
      (node (ref "S1") (pin "3") (pinfunction "NO_3") (pintype "passive"))
    )
    (net (code "33") (name "Net-(S2-COM)") (class "Default")
      (node (ref "S2") (pin "2") (pinfunction "COM_2") (pintype "passive"))
      (node (ref "U2") (pin "23") (pinfunction "CS_23") (pintype "passive"))
    )
    (net (code "34") (name "Net-(S2-NC)") (class "Default")
      (node (ref "R2") (pin "1") (pinfunction "1_1") (pintype "passive"))
      (node (ref "S2") (pin "1") (pinfunction "NC_1") (pintype "passive"))
    )
    (net (code "35") (name "Net-(S2-NO)") (class "Default")
      (node (ref "R4") (pin "1") (pinfunction "1_1") (pintype "passive"))
      (node (ref "S2") (pin "3") (pinfunction "NO_3") (pintype "passive"))
    )
    (net (code "36") (name "Net-(S3-NC)") (class "Default")
      (node (ref "R15") (pin "1") (pinfunction "1_1") (pintype "passive"))
      (node (ref "S3") (pin "1") (pinfunction "NC_1") (pintype "passive"))
    )
    (net (code "37") (name "Net-(S3-NO)") (class "Default")
      (node (ref "R16") (pin "1") (pinfunction "1_1") (pintype "passive"))
      (node (ref "S3") (pin "3") (pinfunction "NO_3") (pintype "passive"))
    )
    (net (code "38") (name "Net-(S4-NC)") (class "Default")
      (node (ref "R17") (pin "1") (pinfunction "1_1") (pintype "passive"))
      (node (ref "S4") (pin "1") (pinfunction "NC_1") (pintype "passive"))
    )
    (net (code "39") (name "Net-(S4-NO)") (class "Default")
      (node (ref "R18") (pin "1") (pinfunction "1_1") (pintype "passive"))
      (node (ref "S4") (pin "3") (pinfunction "NO_3") (pintype "passive"))
    )
    (net (code "40") (name "Net-(U1A-CLREF)") (class "Default")
      (node (ref "R7") (pin "2") (pinfunction "2_2") (pintype "passive"))
      (node (ref "U1") (pin "24") (pinfunction "CLREF_24") (pintype "passive"))
    )
    (net (code "41") (name "Net-(U1A-Gate)") (class "Default")
      (node (ref "C12") (pin "2") (pinfunction "2_2") (pintype "passive"))
      (node (ref "U1") (pin "17") (pinfunction "Gate_17") (pintype "passive"))
    )
    (net (code "42") (name "Net-(U1A-SS)") (class "Default")
      (node (ref "C5") (pin "2") (pinfunction "2_2") (pintype "passive"))
      (node (ref "U1") (pin "19") (pinfunction "SS_19") (pintype "passive"))
    )
    (net (code "43") (name "Net-(U1A-VINF)") (class "Default")
      (node (ref "C9") (pin "2") (pinfunction "2_2") (pintype "passive"))
      (node (ref "R13") (pin "1") (pinfunction "1_1") (pintype "passive"))
      (node (ref "U1") (pin "7") (pinfunction "VINF_7") (pintype "power_in"))
    )
    (net (code "44") (name "Net-(U2A-CLREF)") (class "Default")
      (node (ref "R8") (pin "2") (pinfunction "2_2") (pintype "passive"))
      (node (ref "U2") (pin "24") (pinfunction "CLREF_24") (pintype "passive"))
    )
    (net (code "45") (name "Net-(U2A-Gate)") (class "Default")
      (node (ref "C11") (pin "2") (pinfunction "2_2") (pintype "passive"))
      (node (ref "U2") (pin "17") (pinfunction "Gate_17") (pintype "passive"))
    )
    (net (code "46") (name "Net-(U2A-SS)") (class "Default")
      (node (ref "C6") (pin "2") (pinfunction "2_2") (pintype "passive"))
      (node (ref "U2") (pin "19") (pinfunction "SS_19") (pintype "passive"))
    )
    (net (code "47") (name "Net-(U2A-VINF)") (class "Default")
      (node (ref "C10") (pin "2") (pinfunction "2_2") (pintype "passive"))
      (node (ref "R14") (pin "1") (pinfunction "1_1") (pintype "passive"))
      (node (ref "U2") (pin "7") (pinfunction "VINF_7") (pintype "power_in"))
    )
    (net (code "48") (name "unconnected-(U1A-NC-Pad1)") (class "Default")
      (node (ref "U1") (pin "1") (pinfunction "NC_1") (pintype "passive+no_connect"))
    )
    (net (code "49") (name "unconnected-(U1A-NC-Pad2)") (class "Default")
      (node (ref "U1") (pin "2") (pinfunction "NC_2") (pintype "passive+no_connect"))
    )
    (net (code "50") (name "unconnected-(U1A-NC-Pad6)") (class "Default")
      (node (ref "U1") (pin "6") (pinfunction "NC_6") (pintype "passive+no_connect"))
    )
    (net (code "51") (name "unconnected-(U1A-NC-Pad8)") (class "Default")
      (node (ref "U1") (pin "8") (pinfunction "NC_8") (pintype "passive+no_connect"))
    )
    (net (code "52") (name "unconnected-(U2A-NC-Pad1)") (class "Default")
      (node (ref "U2") (pin "1") (pinfunction "NC_1") (pintype "passive+no_connect"))
    )
    (net (code "53") (name "unconnected-(U2A-NC-Pad2)") (class "Default")
      (node (ref "U2") (pin "2") (pinfunction "NC_2") (pintype "passive+no_connect"))
    )
    (net (code "54") (name "unconnected-(U2A-NC-Pad6)") (class "Default")
      (node (ref "U2") (pin "6") (pinfunction "NC_6") (pintype "passive+no_connect"))
    )
    (net (code "55") (name "unconnected-(U2A-NC-Pad8)") (class "Default")
      (node (ref "U2") (pin "8") (pinfunction "NC_8") (pintype "passive+no_connect"))
    )
  )
)
